# PWMDriver.net
KiCad netlist of a schematic drawn in Altium Designer
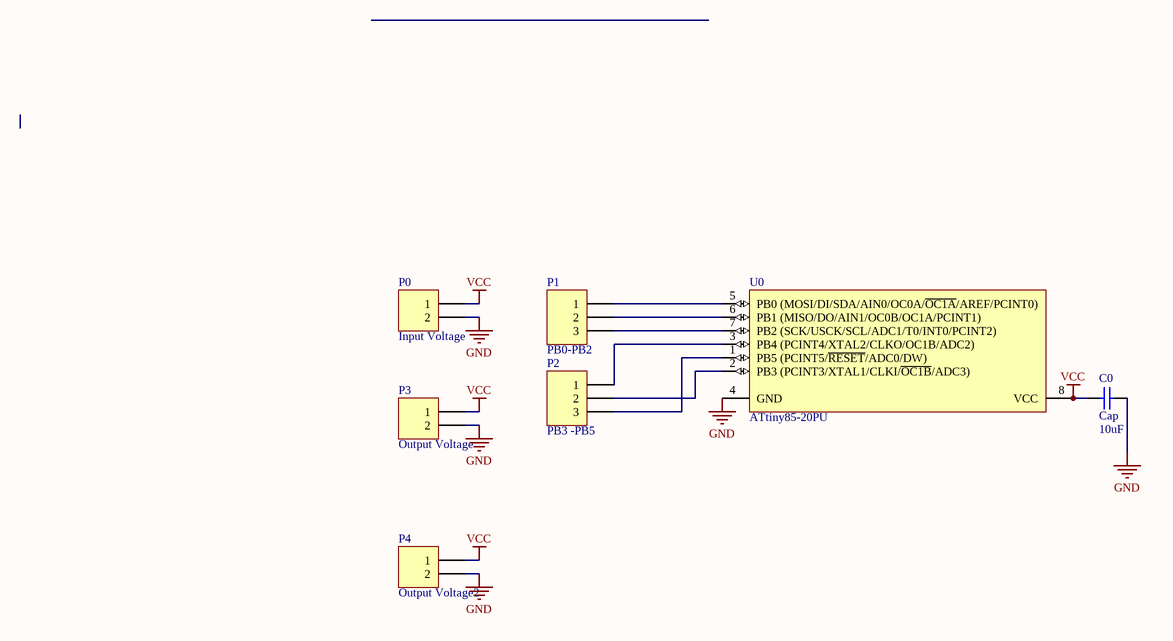
[diagram p0: PWMDriver.SchDoc]

(export (version "E")
  (design (tool "Eeschema 10.0.6"))
  (components
    (comp (ref "C0")
      (value "Cap")
      (footprint "RAD-0.3")
      (description "Capacitor")
      (fields (field (name "ALTIUM_VALUE") "10uF") (field (name "PUBLISHER") "Altium Limited"))
      (libsource (lib "Miscellaneous Devices") (part "Cap"))
    )
    (comp (ref "P0")
      (value "Input Voltage")
      (footprint "HDR1X2")
      (description "Header, 2-Pin")
      (fields (field (name "PUBLISHER") "Altium Limited"))
      (libsource (lib "Miscellaneous Connectors") (part "Header 2"))
    )
    (comp (ref "P1")
      (value "PB0-PB2")
      (footprint "HDR1X3")
      (description "Header, 3-Pin")
      (fields (field (name "PUBLISHER") "Altium Limited"))
      (libsource (lib "Miscellaneous Connectors") (part "Header 3"))
    )
    (comp (ref "P2")
      (value "PB3 -PB5")
      (footprint "HDR1X3")
      (description "Header, 3-Pin")
      (fields (field (name "PUBLISHER") "Altium Limited"))
      (libsource (lib "Miscellaneous Connectors") (part "Header 3"))
    )
    (comp (ref "P3")
      (value "Output Voltage")
      (footprint "HDR1X2")
      (description "Header, 2-Pin")
      (fields (field (name "PUBLISHER") "Altium Limited"))
      (libsource (lib "Miscellaneous Connectors") (part "Header 2"))
    )
    (comp (ref "P4")
      (value "Output Voltage2")
      (footprint "HDR1X2")
      (description "Header, 2-Pin")
      (fields (field (name "PUBLISHER") "Altium Limited"))
      (libsource (lib "Miscellaneous Connectors") (part "Header 2"))
    )
    (comp (ref "U0")
      (value "ATtiny85-20PU")
      (footprint "8P3")
      (fields (field (name "PUBLISHER") "Altium Limited"))
      (libsource (lib "Atmel Microcontroller 8-Bit tinyAVR") (part "ATtiny85-20PU"))
    )
  )
  (nets
    (net (code "1") (name "GND") (class "Default")
      (node (ref "C0") (pin "2") (pinfunction "2_2") (pintype "passive"))
      (node (ref "P0") (pin "2") (pinfunction "2_2") (pintype "passive"))
      (node (ref "P3") (pin "2") (pinfunction "2_2") (pintype "passive"))
      (node (ref "P4") (pin "2") (pinfunction "2_2") (pintype "passive"))
      (node (ref "U0") (pin "4") (pinfunction "GND_4") (pintype "power_in"))
    )
    (net (code "2") (name "Net-(U0-PB0_(MOSI{slash}DI{slash}SDA{slash}AIN0{slash}OC0A{slash}~{OC1A}{slash}AREF{slash}PCINT0))") (class "Default")
      (node (ref "P1") (pin "1") (pinfunction "1_1") (pintype "passive"))
      (node (ref "U0") (pin "5") (pinfunction "PB0_(MOSI/DI/SDA/AIN0/OC0A/~{OC1A}/AREF/PCINT0)_5") (pintype "bidirectional"))
    )
    (net (code "3") (name "Net-(U0-PB1_(MISO{slash}DO{slash}AIN1{slash}OC0B{slash}OC1A{slash}PCINT1))") (class "Default")
      (node (ref "P1") (pin "2") (pinfunction "2_2") (pintype "passive"))
      (node (ref "U0") (pin "6") (pinfunction "PB1_(MISO/DO/AIN1/OC0B/OC1A/PCINT1)_6") (pintype "bidirectional"))
    )
    (net (code "4") (name "Net-(U0-PB2_(SCK{slash}USCK{slash}SCL{slash}ADC1{slash}T0{slash}INT0{slash}PCINT2))") (class "Default")
      (node (ref "P1") (pin "3") (pinfunction "3_3") (pintype "passive"))
      (node (ref "U0") (pin "7") (pinfunction "PB2_(SCK/USCK/SCL/ADC1/T0/INT0/PCINT2)_7") (pintype "bidirectional"))
    )
    (net (code "5") (name "Net-(U0-PB3_(PCINT3{slash}XTAL1{slash}CLKI{slash}~{OC1B}{slash}ADC3))") (class "Default")
      (node (ref "P2") (pin "2") (pinfunction "2_2") (pintype "passive"))
      (node (ref "U0") (pin "2") (pinfunction "PB3_(PCINT3/XTAL1/CLKI/~{OC1B}/ADC3)_2") (pintype "bidirectional"))
    )
    (net (code "6") (name "Net-(U0-PB4_(PCINT4{slash}XTAL2{slash}CLKO{slash}OC1B{slash}ADC2))") (class "Default")
      (node (ref "P2") (pin "1") (pinfunction "1_1") (pintype "passive"))
      (node (ref "U0") (pin "3") (pinfunction "PB4_(PCINT4/XTAL2/CLKO/OC1B/ADC2)_3") (pintype "bidirectional"))
    )
    (net (code "7") (name "Net-(U0-PB5_(PCINT5{slash}~{RESET}{slash}ADC0{slash}DW))") (class "Default")
      (node (ref "P2") (pin "3") (pinfunction "3_3") (pintype "passive"))
      (node (ref "U0") (pin "1") (pinfunction "PB5_(PCINT5/~{RESET}/ADC0/DW)_1") (pintype "bidirectional"))
    )
    (net (code "8") (name "VCC") (class "Default")
      (node (ref "C0") (pin "1") (pinfunction "1_1") (pintype "passive"))
      (node (ref "P0") (pin "1") (pinfunction "1_1") (pintype "passive"))
      (node (ref "P3") (pin "1") (pinfunction "1_1") (pintype "passive"))
      (node (ref "P4") (pin "1") (pinfunction "1_1") (pintype "passive"))
      (node (ref "U0") (pin "8") (pinfunction "VCC_8") (pintype "power_in"))
    )
  )
)
